# txpreamp6.net
KiCad netlist of a schematic drawn in Altium Designer
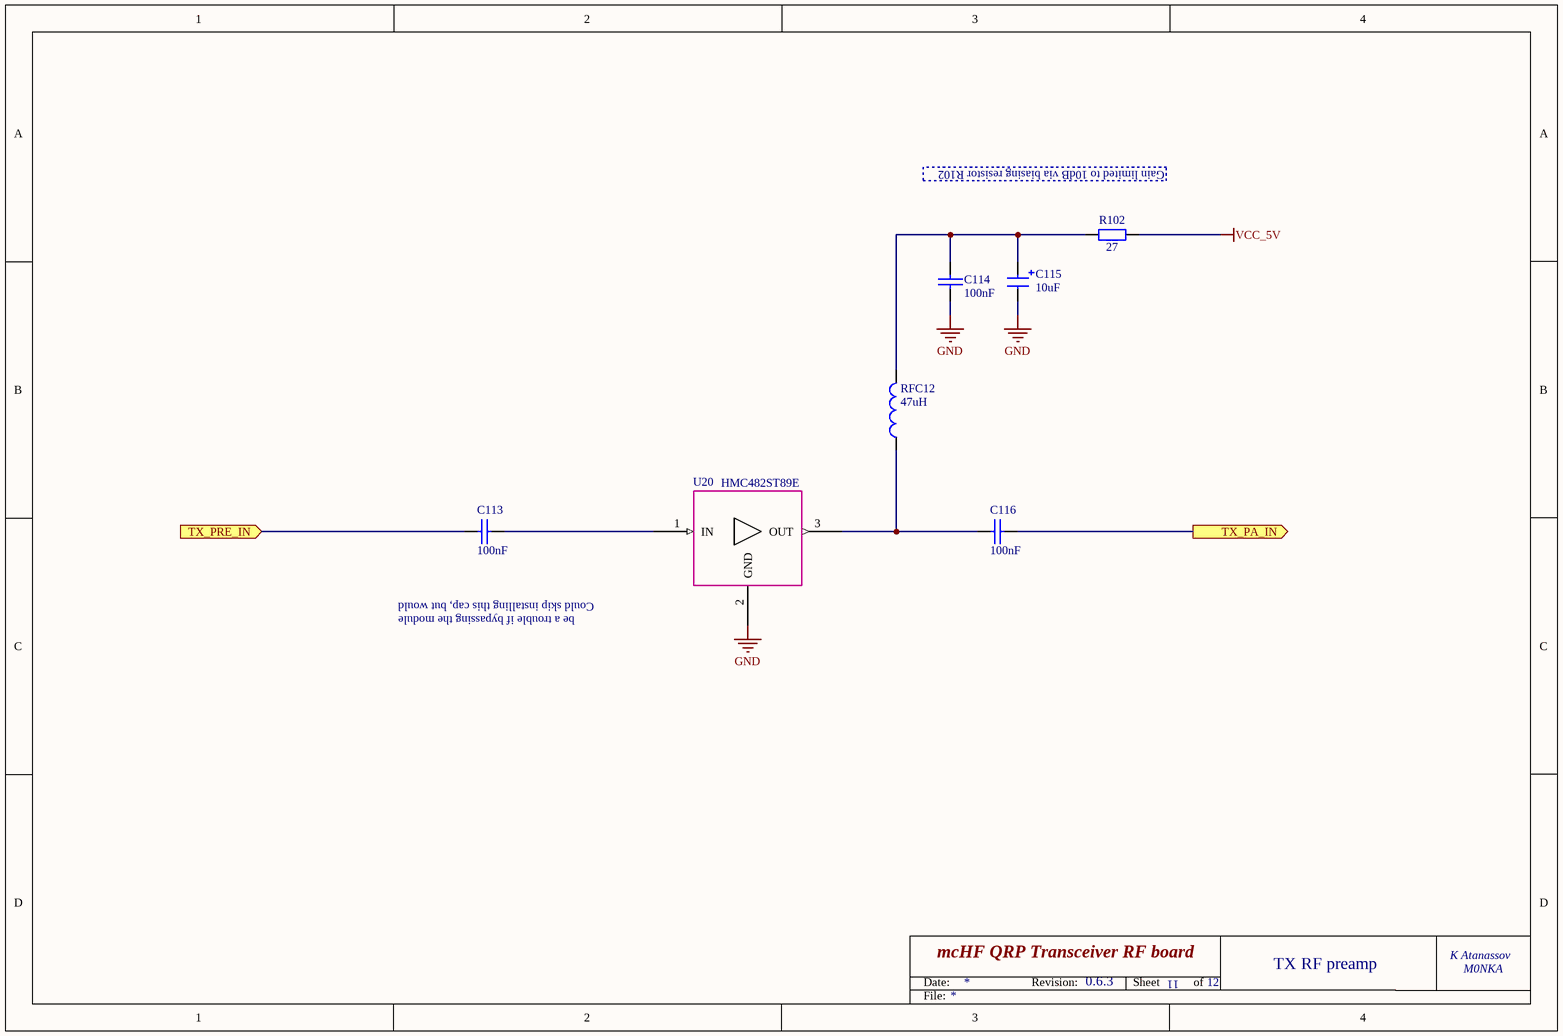
[diagram p0: txpreamp6.SchDoc]

(export (version "E")
  (design (tool "Eeschema 10.0.6"))
  (components
    (comp (ref "C113")
      (value "100nF")
      (footprint "0805-Pro")
      (description "Capacitor")
      (libsource (lib "*") (part "CAP"))
    )
    (comp (ref "C114")
      (value "100nF")
      (footprint "0805-Pro")
      (description "Capacitor")
      (libsource (lib "*") (part "CAP"))
    )
    (comp (ref "C115")
      (value "10uF")
      (footprint "1206_Elec_Cap_N")
      (description "Electrolitic capacitor")
      (libsource (lib "mcHF_rf") (part "CAP-POL"))
    )
    (comp (ref "C116")
      (value "100nF")
      (footprint "0805-Pro")
      (description "Capacitor")
      (libsource (lib "*") (part "CAP"))
    )
    (comp (ref "R102")
      (value "27")
      (footprint "1206")
      (description "Resistor")
      (libsource (lib "mcHF_rf") (part "RES"))
    )
    (comp (ref "RFC12")
      (value "47uH")
      (footprint "0805-Pro")
      (description "INDUCTOR, SIGNAL LINE, 4.7UH, 1005")
      (libsource (lib "mcHF_rf") (part "TDK-NLV25T"))
    )
    (comp (ref "U20")
      (value "HMC482ST89E")
      (footprint "SOT89L_new")
      (description "MMIC AMPLIFIER")
      (libsource (lib "mcHF_rf") (part "HMS482ST89E"))
    )
  )
  (nets
    (net (code "1") (name "/TX_PA_IN") (class "Default")
      (node (ref "C116") (pin "1") (pinfunction "1_1") (pintype "passive"))
    )
    (net (code "2") (name "/TX_PRE_IN") (class "Default")
      (node (ref "C113") (pin "2") (pinfunction "2_2") (pintype "passive"))
    )
    (net (code "3") (name "GND") (class "Default")
      (node (ref "C114") (pin "2") (pinfunction "2_2") (pintype "passive"))
      (node (ref "C115") (pin "2") (pinfunction "2_2") (pintype "passive"))
      (node (ref "U20") (pin "2") (pinfunction "GND_2") (pintype "power_in"))
    )
    (net (code "4") (name "Net-(C114-Pad1)") (class "Default")
      (node (ref "C114") (pin "1") (pinfunction "1_1") (pintype "passive"))
      (node (ref "C115") (pin "1") (pinfunction "1_1") (pintype "passive"))
      (node (ref "R102") (pin "2") (pinfunction "2_2") (pintype "passive"))
      (node (ref "RFC12") (pin "2") (pinfunction "2_2") (pintype "passive"))
    )
    (net (code "5") (name "Net-(U20-IN)") (class "Default")
      (node (ref "C113") (pin "1") (pinfunction "1_1") (pintype "passive"))
      (node (ref "U20") (pin "1") (pinfunction "IN_1") (pintype "input"))
    )
    (net (code "6") (name "Net-(U20-OUT)") (class "Default")
      (node (ref "C116") (pin "2") (pinfunction "2_2") (pintype "passive"))
      (node (ref "RFC12") (pin "1") (pinfunction "1_1") (pintype "passive"))
      (node (ref "U20") (pin "3") (pinfunction "OUT_3") (pintype "output"))
    )
    (net (code "7") (name "VCC_5V") (class "Default")
      (node (ref "R102") (pin "1") (pinfunction "1_1") (pintype "passive"))
    )
  )
)
